# Main_MCU_Page_1.net
KiCad netlist of a schematic drawn in Altium Designer
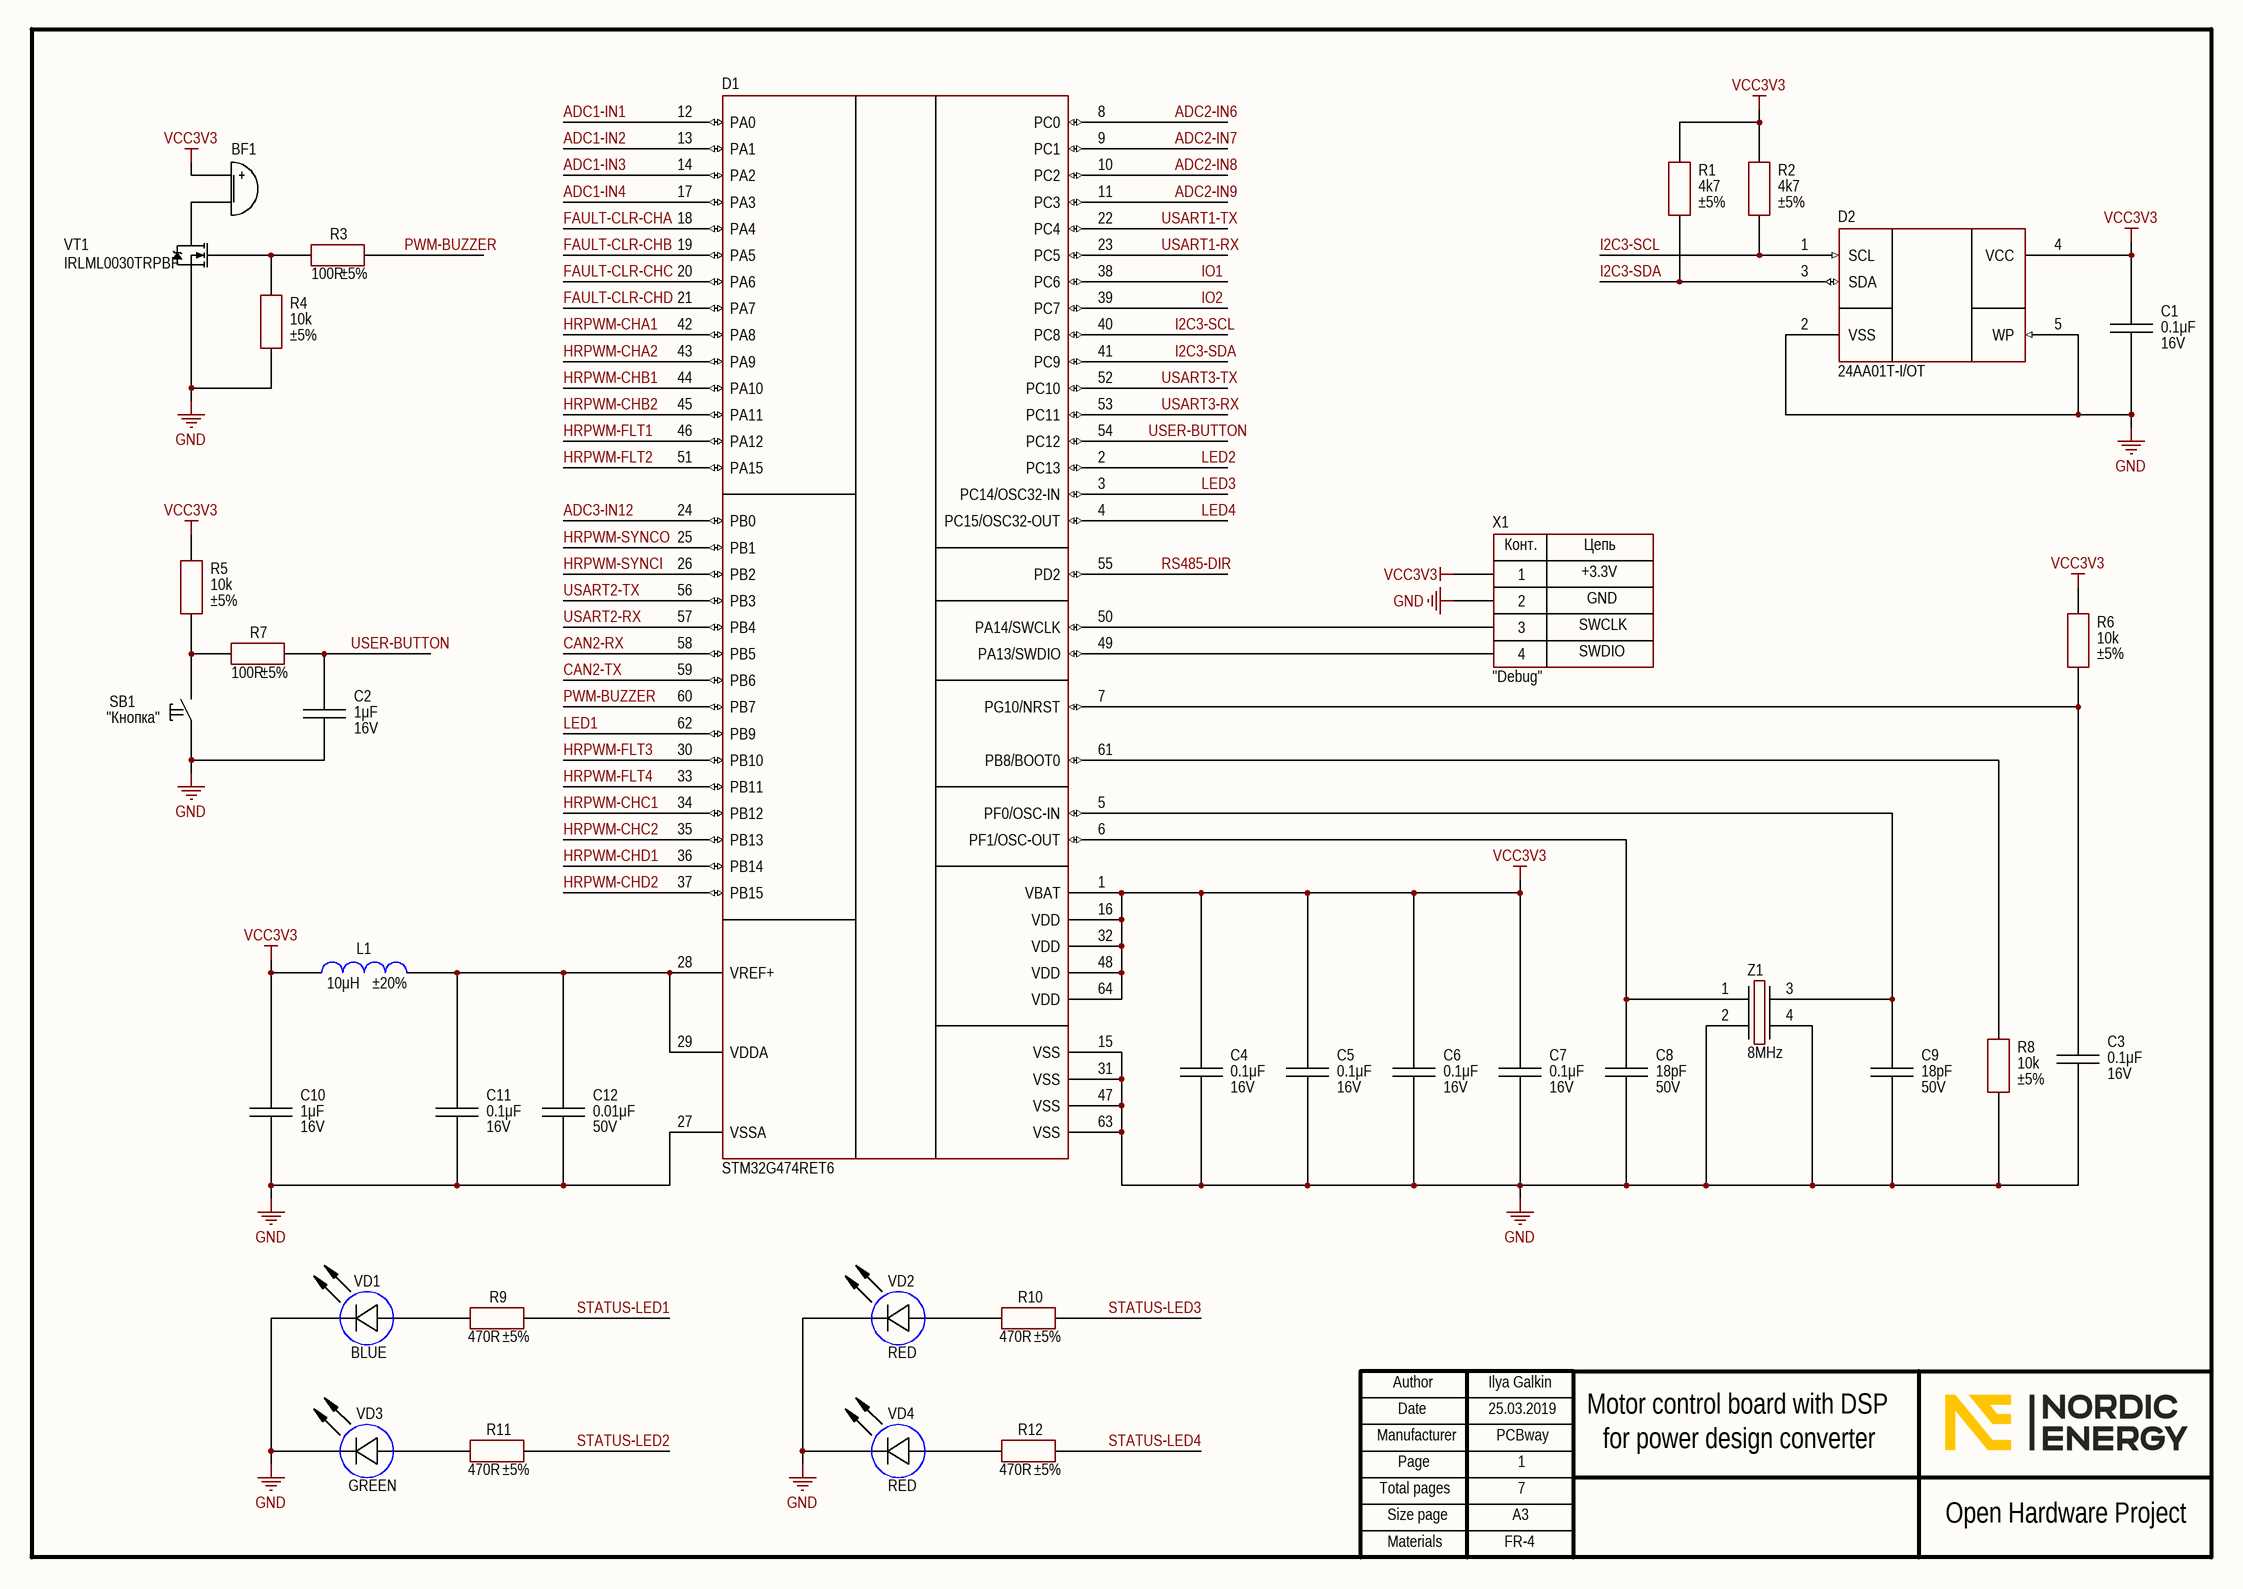
[diagram p0: Main MCU. Page 1.SchDoc]

(export (version "E")
  (design (tool "Eeschema 10.0.6"))
  (components
    (comp (ref "BF1")
      (value "~")
      (footprint "BUZ: AT-0927-TT-6-R")
      (fields
        (field (name "MANUFACTURER") "PUI Audio")
        (field (name "VALUEMANUFACTURERPARTNUMBER") "DIP switch, 2.73 kHz, 3VDC, 80mA, -20...+70°C")
        (field (name "PARTNUMBER") "AT-0927-TT-6-R")
      )
      (libsource (lib "Electromechanics") (part "Buzzer"))
    )
    (comp (ref "C1")
      (value "0.1μF")
      (footprint "CAP: 0805")
      (fields
        (field (name "MANUFACTURER") "Yageo")
        (field (name "PARTNUMBER") "CC0805KRX7R7BB104")
        (field (name "VALUEMANUFACTURERPARTNUMBER") "Ceramic capacitor, 0.1μF, X7R, ±10%, 16V, 0805, -55...+125°C")
        (field (name "VOLTAGE") "16V")
      )
      (libsource (lib "Capacitor") (part "Ceramic_0805"))
    )
    (comp (ref "C2")
      (value "1μF")
      (footprint "CAP: 0805")
      (fields
        (field (name "MANUFACTURER") "Yageo")
        (field (name "PARTNUMBER") "CC0805KKX7R7BB105")
        (field (name "VALUEMANUFACTURERPARTNUMBER") "Ceramic capacitor, 1μF, X7R, ±10%, 16V, 0805, -55...+125°C")
        (field (name "VOLTAGE") "16V")
      )
      (libsource (lib "Capacitor") (part "Ceramic_0805"))
    )
    (comp (ref "C3")
      (value "0.1μF")
      (footprint "CAP: 0805")
      (fields
        (field (name "MANUFACTURER") "Yageo")
        (field (name "PARTNUMBER") "CC0805KRX7R7BB104")
        (field (name "VALUEMANUFACTURERPARTNUMBER") "Ceramic capacitor, 0.1μF, X7R, ±10%, 16V, 0805, -55...+125°C")
        (field (name "VOLTAGE") "16V")
      )
      (libsource (lib "Capacitor") (part "Ceramic_0805"))
    )
    (comp (ref "C4")
      (value "0.1μF")
      (footprint "CAP: 0805")
      (fields
        (field (name "MANUFACTURER") "Yageo")
        (field (name "PARTNUMBER") "CC0805KRX7R7BB104")
        (field (name "VALUEMANUFACTURERPARTNUMBER") "Ceramic capacitor, 0.1μF, X7R, ±10%, 16V, 0805, -55...+125°C")
        (field (name "VOLTAGE") "16V")
      )
      (libsource (lib "Capacitor") (part "Ceramic_0805"))
    )
    (comp (ref "C5")
      (value "0.1μF")
      (footprint "CAP: 0805")
      (fields
        (field (name "MANUFACTURER") "Yageo")
        (field (name "PARTNUMBER") "CC0805KRX7R7BB104")
        (field (name "VALUEMANUFACTURERPARTNUMBER") "Ceramic capacitor, 0.1μF, X7R, ±10%, 16V, 0805, -55...+125°C")
        (field (name "VOLTAGE") "16V")
      )
      (libsource (lib "Capacitor") (part "Ceramic_0805"))
    )
    (comp (ref "C6")
      (value "0.1μF")
      (footprint "CAP: 0805")
      (fields
        (field (name "MANUFACTURER") "Yageo")
        (field (name "PARTNUMBER") "CC0805KRX7R7BB104")
        (field (name "VALUEMANUFACTURERPARTNUMBER") "Ceramic capacitor, 0.1μF, X7R, ±10%, 16V, 0805, -55...+125°C")
        (field (name "VOLTAGE") "16V")
      )
      (libsource (lib "Capacitor") (part "Ceramic_0805"))
    )
    (comp (ref "C7")
      (value "0.1μF")
      (footprint "CAP: 0805")
      (fields
        (field (name "MANUFACTURER") "Yageo")
        (field (name "PARTNUMBER") "CC0805KRX7R7BB104")
        (field (name "VALUEMANUFACTURERPARTNUMBER") "Ceramic capacitor, 0.1μF, X7R, ±10%, 16V, 0805, -55...+125°C")
        (field (name "VOLTAGE") "16V")
      )
      (libsource (lib "Capacitor") (part "Ceramic_0805"))
    )
    (comp (ref "C8")
      (value "18pF")
      (footprint "CAP: 0805")
      (fields
        (field (name "MANUFACTURER") "Yageo")
        (field (name "PARTNUMBER") "CC0805JRNPO9BN180")
        (field (name "VALUEMANUFACTURERPARTNUMBER") "Ceramic capacitor, 18pF, NPO, ±10%, 50V, 0805, -55...+125°C")
        (field (name "VOLTAGE") "50V")
      )
      (libsource (lib "Capacitor") (part "Ceramic_0805"))
    )
    (comp (ref "C9")
      (value "18pF")
      (footprint "CAP: 0805")
      (fields
        (field (name "MANUFACTURER") "Yageo")
        (field (name "PARTNUMBER") "CC0805JRNPO9BN180")
        (field (name "VALUEMANUFACTURERPARTNUMBER") "Ceramic capacitor, 18pF, NPO, ±10%, 50V, 0805, -55...+125°C")
        (field (name "VOLTAGE") "50V")
      )
      (libsource (lib "Capacitor") (part "Ceramic_0805"))
    )
    (comp (ref "C10")
      (value "1μF")
      (footprint "CAP: 0805")
      (fields
        (field (name "MANUFACTURER") "Yageo")
        (field (name "PARTNUMBER") "CC0805KKX7R7BB105")
        (field (name "VALUEMANUFACTURERPARTNUMBER") "Ceramic capacitor, 1μF, X7R, ±10%, 16V, 0805, -55...+125°C")
        (field (name "VOLTAGE") "16V")
      )
      (libsource (lib "Capacitor") (part "Ceramic_0805"))
    )
    (comp (ref "C11")
      (value "0.1μF")
      (footprint "CAP: 0805")
      (fields
        (field (name "MANUFACTURER") "Yageo")
        (field (name "PARTNUMBER") "CC0805KRX7R7BB104")
        (field (name "VALUEMANUFACTURERPARTNUMBER") "Ceramic capacitor, 0.1μF, X7R, ±10%, 16V, 0805, -55...+125°C")
        (field (name "VOLTAGE") "16V")
      )
      (libsource (lib "Capacitor") (part "Ceramic_0805"))
    )
    (comp (ref "C12")
      (value "0.01μF")
      (footprint "CAP: 0805")
      (fields
        (field (name "MANUFACTURER") "Yageo")
        (field (name "PARTNUMBER") "CC0805KRX7R9BB103")
        (field (name "VALUEMANUFACTURERPARTNUMBER") "Ceramic capacitor, 0.01μF, X7R, ±10%, 50V, 0805, -55...+125°C")
        (field (name "VOLTAGE") "50V")
      )
      (libsource (lib "Capacitor") (part "Ceramic_0805"))
    )
    (comp (ref "D1")
      (value "~")
      (footprint "64-LQFP")
      (description "Cortex-M4")
      (fields
        (field (name "MANUFACTURER") "STMicroelectronics")
        (field (name "VALUEMANUFACTURERPARTNUMBER") "IC microcontroller, 32-Bit, Cortex-M4, 170MHz, 512KB, 128KB, 1.71...3.6V, -40...+85°C, 64-LQFP")
        (field (name "PARTNUMBER") "STM32G474RET6")
      )
      (libsource (lib "IC. MCU") (part "STM32G474RET6"))
    )
    (comp (ref "D2")
      (value "~")
      (footprint "SOT23-5")
      (description "EEPROM")
      (fields
        (field (name "MANUFACTURER") "Microchip Technology")
        (field (name "VALUEMANUFACTURERPARTNUMBER") "IC memory, EEPROM, 1KB (128x8), 400 kHz, I2C, 1.7...5.5V, -40...+85°C, SOT-23-5")
        (field (name "PARTNUMBER") "24AA01T-I/OT")
      )
      (libsource (lib "IC. Memory") (part "24AA01T"))
    )
    (comp (ref "L1")
      (value "10μH")
      (footprint "IND: 0805")
      (fields
        (field (name "MANUFACTURER") "Murata Electronics")
        (field (name "PARTNUMBER") "LQM21FN100M70L")
        (field (name "VALUEMANUFACTURERPARTNUMBER") "Fixed inductor, 10μH, ±20%, 0805, 100mA, -55...+125°C")
        (field (name "TOLERANCE") "±20%")
      )
      (libsource (lib "Inductor") (part "Inductor_0805"))
    )
    (comp (ref "R1")
      (value "4k7")
      (footprint "RES: 0805")
      (fields
        (field (name "MANUFACTURER") "Yageo")
        (field (name "PARTNUMBER") "RC0805JR-074K7L")
        (field (name "VALUEMANUFACTURERPARTNUMBER") "Resistor film, 4k7, ±5%, 0805, 0.125W, -55...+125°C")
        (field (name "TOLERANCE") "±5%")
      )
      (libsource (lib "Resistor") (part "Resistor_0805"))
    )
    (comp (ref "R2")
      (value "4k7")
      (footprint "RES: 0805")
      (fields
        (field (name "MANUFACTURER") "Yageo")
        (field (name "PARTNUMBER") "RC0805JR-074K7L")
        (field (name "VALUEMANUFACTURERPARTNUMBER") "Resistor film, 4k7, ±5%, 0805, 0.125W, -55...+125°C")
        (field (name "TOLERANCE") "±5%")
      )
      (libsource (lib "Resistor") (part "Resistor_0805"))
    )
    (comp (ref "R3")
      (value "100R")
      (footprint "RES: 0805")
      (fields
        (field (name "MANUFACTURER") "Yageo")
        (field (name "PARTNUMBER") "RC0805JR-07100RL")
        (field (name "VALUEMANUFACTURERPARTNUMBER") "Resistor film, 100R, ±5%, 0805, 0.125W, -55...+125°C")
        (field (name "TOLERANCE") "±5%")
      )
      (libsource (lib "") (part "Resistor_0805_1"))
    )
    (comp (ref "R4")
      (value "10k")
      (footprint "RES: 0805")
      (fields
        (field (name "MANUFACTURER") "Yageo")
        (field (name "PARTNUMBER") "RC0805JR-0710KL")
        (field (name "VALUEMANUFACTURERPARTNUMBER") "Resistor film, 10k, ±5%, 0805, 0.125W, -55...+125°C")
        (field (name "TOLERANCE") "±5%")
      )
      (libsource (lib "Resistor") (part "Resistor_0805"))
    )
    (comp (ref "R5")
      (value "10k")
      (footprint "RES: 0805")
      (fields
        (field (name "MANUFACTURER") "Yageo")
        (field (name "PARTNUMBER") "RC0805JR-0710KL")
        (field (name "VALUEMANUFACTURERPARTNUMBER") "Resistor film, 10k, ±5%, 0805, 0.125W, -55...+125°C")
        (field (name "TOLERANCE") "±5%")
      )
      (libsource (lib "Resistor") (part "Resistor_0805"))
    )
    (comp (ref "R6")
      (value "10k")
      (footprint "RES: 0805")
      (fields
        (field (name "MANUFACTURER") "Yageo")
        (field (name "PARTNUMBER") "RC0805JR-0710KL")
        (field (name "VALUEMANUFACTURERPARTNUMBER") "Resistor film, 10k, ±5%, 0805, 0.125W, -55...+125°C")
        (field (name "TOLERANCE") "±5%")
      )
      (libsource (lib "Resistor") (part "Resistor_0805"))
    )
    (comp (ref "R7")
      (value "100R")
      (footprint "RES: 0805")
      (fields
        (field (name "MANUFACTURER") "Yageo")
        (field (name "PARTNUMBER") "RC0805JR-07100RL")
        (field (name "VALUEMANUFACTURERPARTNUMBER") "Resistor film, 100R, ±5%, 0805, 0.125W, -55...+125°C")
        (field (name "TOLERANCE") "±5%")
      )
      (libsource (lib "") (part "Resistor_0805_1"))
    )
    (comp (ref "R8")
      (value "10k")
      (footprint "RES: 0805")
      (fields
        (field (name "MANUFACTURER") "Yageo")
        (field (name "PARTNUMBER") "RC0805JR-0710KL")
        (field (name "VALUEMANUFACTURERPARTNUMBER") "Resistor film, 10k, ±5%, 0805, 0.125W, -55...+125°C")
        (field (name "TOLERANCE") "±5%")
      )
      (libsource (lib "Resistor") (part "Resistor_0805"))
    )
    (comp (ref "R9")
      (value "470R")
      (footprint "RES: 0805")
      (fields
        (field (name "MANUFACTURER") "Yageo")
        (field (name "PARTNUMBER") "RC0805JR-07470RL")
        (field (name "VALUEMANUFACTURERPARTNUMBER") "Resistor film, 470R, ±5%, 0805, 0.125W, -55...+125°C")
        (field (name "TOLERANCE") "±5%")
      )
      (libsource (lib "") (part "Resistor_0805_1"))
    )
    (comp (ref "R10")
      (value "470R")
      (footprint "RES: 0805")
      (fields
        (field (name "MANUFACTURER") "Yageo")
        (field (name "PARTNUMBER") "RC0805JR-07470RL")
        (field (name "VALUEMANUFACTURERPARTNUMBER") "Resistor film, 470R, ±5%, 0805, 0.125W, -55...+125°C")
        (field (name "TOLERANCE") "±5%")
      )
      (libsource (lib "") (part "Resistor_0805_1"))
    )
    (comp (ref "R11")
      (value "470R")
      (footprint "RES: 0805")
      (fields
        (field (name "MANUFACTURER") "Yageo")
        (field (name "PARTNUMBER") "RC0805JR-07470RL")
        (field (name "VALUEMANUFACTURERPARTNUMBER") "Resistor film, 470R, ±5%, 0805, 0.125W, -55...+125°C")
        (field (name "TOLERANCE") "±5%")
      )
      (libsource (lib "") (part "Resistor_0805_1"))
    )
    (comp (ref "R12")
      (value "470R")
      (footprint "RES: 0805")
      (fields
        (field (name "MANUFACTURER") "Yageo")
        (field (name "PARTNUMBER") "RC0805JR-07470RL")
        (field (name "VALUEMANUFACTURERPARTNUMBER") "Resistor film, 470R, ±5%, 0805, 0.125W, -55...+125°C")
        (field (name "TOLERANCE") "±5%")
      )
      (libsource (lib "") (part "Resistor_0805_1"))
    )
    (comp (ref "SB1")
      (value "~")
      (footprint "BUT: 6x6 SMD")
      (fields
        (field (name "MANUFACTURER") "TE Connectivity")
        (field (name "VALUEMANUFACTURERPARTNUMBER") "Tactile button, 6x6mm")
        (field (name "PARTNUMBER") "FSM2JSMAATR")
        (field (name "COMMENTTEXT") "\"Кнопка\"")
      )
      (libsource (lib "Electromechanics") (part "Button_tactile"))
    )
    (comp (ref "VD1")
      (value "~")
      (footprint "LED: 0805B")
      (fields
        (field (name "MANUFACTURER") "Wurth")
        (field (name "VALUEMANUFACTURERPARTNUMBER") "LED, 20mA, 3.2V, 0805, -55...+150°C")
        (field (name "PARTNUMBER") "150080BS75000")
        (field (name "COLOR") "BLUE")
      )
      (libsource (lib "Diode") (part "LED_single"))
    )
    (comp (ref "VD2")
      (value "~")
      (footprint "LED: 0805R")
      (fields
        (field (name "MANUFACTURER") "Wurth")
        (field (name "VALUEMANUFACTURERPARTNUMBER") "LED, 20mA, 2V, 0805, -55...+150°C")
        (field (name "PARTNUMBER") "150080RS75000")
        (field (name "COLOR") "RED")
      )
      (libsource (lib "Diode") (part "LED_single"))
    )
    (comp (ref "VD3")
      (value "~")
      (footprint "LED: 0603G")
      (fields
        (field (name "MANUFACTURER") "Wurth")
        (field (name "VALUEMANUFACTURERPARTNUMBER") "LED, 20mA, 2V, 0805, -55...+150°C")
        (field (name "PARTNUMBER") "150080VS75000")
        (field (name "COLOR") "GREEN")
      )
      (libsource (lib "Diode") (part "LED_single"))
    )
    (comp (ref "VD4")
      (value "~")
      (footprint "LED: 0805R")
      (fields
        (field (name "MANUFACTURER") "Wurth")
        (field (name "VALUEMANUFACTURERPARTNUMBER") "LED, 20mA, 2V, 0805, -55...+150°C")
        (field (name "PARTNUMBER") "150080RS75000")
        (field (name "COLOR") "RED")
      )
      (libsource (lib "Diode") (part "LED_single"))
    )
    (comp (ref "VT1")
      (value "~")
      (footprint "SOT23")
      (fields
        (field (name "MANUFACTURER") "Infineon Technologies")
        (field (name "VALUEMANUFACTURERPARTNUMBER") "MOSFET N-channel transistor, 30V, 5.3A, 2.6nC, 2.5W, 27mOhm, 382pF, SOT-23, -55...+150°C")
        (field (name "PARTNUMBER") "IRLML0030TRPBF")
      )
      (libsource (lib "Transistor") (part "MOSFET_N_132"))
    )
    (comp (ref "X1")
      (value "~")
      (footprint "CON: SM04B-GHS")
      (fields
        (field (name "MANUFACTURER") "JST")
        (field (name "VALUEMANUFACTURERPARTNUMBER") "Connector, 4pin, 1.25mm, 50VDC, 1A")
        (field (name "PARTNUMBER") "SM04B-GHS")
        (field (name "COMMENTTEXT") "\"Debug\"")
      )
      (libsource (lib "Connector") (part "Connector_SM04B"))
    )
    (comp (ref "Z1")
      (value "~")
      (footprint "OSC: 5032")
      (fields
        (field (name "MANUFACTURER") "Diodes Incorporated")
        (field (name "PARTNUMBER") "ABM3B-8.000MHZ-B2-T")
        (field (name "VALUEMANUFACTURERPARTNUMBER") "Crystal, 8MHz, 18pF, ±30ppm, case 5032, -20...+70°C")
        (field (name "FREQUENCY") "8MHz")
      )
      (libsource (lib "Oscilator") (part "Crystal_5032"))
    )
  )
  (nets
    (net (code "1") (name "/ADC1-IN1") (class "Default")
      (node (ref "D1") (pin "12") (pinfunction "PA0_12") (pintype "bidirectional"))
    )
    (net (code "2") (name "/ADC1-IN2") (class "Default")
      (node (ref "D1") (pin "13") (pinfunction "PA1_13") (pintype "bidirectional"))
    )
    (net (code "3") (name "/ADC1-IN3") (class "Default")
      (node (ref "D1") (pin "14") (pinfunction "PA2_14") (pintype "bidirectional"))
    )
    (net (code "4") (name "/ADC1-IN4") (class "Default")
      (node (ref "D1") (pin "17") (pinfunction "PA3_17") (pintype "bidirectional"))
    )
    (net (code "5") (name "/ADC2-IN6") (class "Default")
      (node (ref "D1") (pin "8") (pinfunction "PC0_8") (pintype "bidirectional"))
    )
    (net (code "6") (name "/ADC2-IN7") (class "Default")
      (node (ref "D1") (pin "9") (pinfunction "PC1_9") (pintype "bidirectional"))
    )
    (net (code "7") (name "/ADC2-IN8") (class "Default")
      (node (ref "D1") (pin "10") (pinfunction "PC2_10") (pintype "bidirectional"))
    )
    (net (code "8") (name "/ADC2-IN9") (class "Default")
      (node (ref "D1") (pin "11") (pinfunction "PC3_11") (pintype "bidirectional"))
    )
    (net (code "9") (name "/ADC3-IN12") (class "Default")
      (node (ref "D1") (pin "24") (pinfunction "PB0_24") (pintype "bidirectional"))
    )
    (net (code "10") (name "/CAN2-RX") (class "Default")
      (node (ref "D1") (pin "58") (pinfunction "PB5_58") (pintype "bidirectional"))
    )
    (net (code "11") (name "/CAN2-TX") (class "Default")
      (node (ref "D1") (pin "59") (pinfunction "PB6_59") (pintype "bidirectional"))
    )
    (net (code "12") (name "/FAULT-CLR-CHA") (class "Default")
      (node (ref "D1") (pin "18") (pinfunction "PA4_18") (pintype "bidirectional"))
    )
    (net (code "13") (name "/FAULT-CLR-CHB") (class "Default")
      (node (ref "D1") (pin "19") (pinfunction "PA5_19") (pintype "bidirectional"))
    )
    (net (code "14") (name "/FAULT-CLR-CHC") (class "Default")
      (node (ref "D1") (pin "20") (pinfunction "PA6_20") (pintype "bidirectional"))
    )
    (net (code "15") (name "/FAULT-CLR-CHD") (class "Default")
      (node (ref "D1") (pin "21") (pinfunction "PA7_21") (pintype "bidirectional"))
    )
    (net (code "16") (name "/HRPWM-CHA1") (class "Default")
      (node (ref "D1") (pin "42") (pinfunction "PA8_42") (pintype "bidirectional"))
    )
    (net (code "17") (name "/HRPWM-CHA2") (class "Default")
      (node (ref "D1") (pin "43") (pinfunction "PA9_43") (pintype "bidirectional"))
    )
    (net (code "18") (name "/HRPWM-CHB1") (class "Default")
      (node (ref "D1") (pin "44") (pinfunction "PA10_44") (pintype "bidirectional"))
    )
    (net (code "19") (name "/HRPWM-CHB2") (class "Default")
      (node (ref "D1") (pin "45") (pinfunction "PA11_45") (pintype "bidirectional"))
    )
    (net (code "20") (name "/HRPWM-CHC1") (class "Default")
      (node (ref "D1") (pin "34") (pinfunction "PB12_34") (pintype "bidirectional"))
    )
    (net (code "21") (name "/HRPWM-CHC2") (class "Default")
      (node (ref "D1") (pin "35") (pinfunction "PB13_35") (pintype "bidirectional"))
    )
    (net (code "22") (name "/HRPWM-CHD1") (class "Default")
      (node (ref "D1") (pin "36") (pinfunction "PB14_36") (pintype "bidirectional"))
    )
    (net (code "23") (name "/HRPWM-CHD2") (class "Default")
      (node (ref "D1") (pin "37") (pinfunction "PB15_37") (pintype "bidirectional"))
    )
    (net (code "24") (name "/HRPWM-FLT1") (class "Default")
      (node (ref "D1") (pin "46") (pinfunction "PA12_46") (pintype "bidirectional"))
    )
    (net (code "25") (name "/HRPWM-FLT2") (class "Default")
      (node (ref "D1") (pin "51") (pinfunction "PA15_51") (pintype "bidirectional"))
    )
    (net (code "26") (name "/HRPWM-FLT3") (class "Default")
      (node (ref "D1") (pin "30") (pinfunction "PB10_30") (pintype "bidirectional"))
    )
    (net (code "27") (name "/HRPWM-FLT4") (class "Default")
      (node (ref "D1") (pin "33") (pinfunction "PB11_33") (pintype "bidirectional"))
    )
    (net (code "28") (name "/HRPWM-SYNCI") (class "Default")
      (node (ref "D1") (pin "26") (pinfunction "PB2_26") (pintype "bidirectional"))
    )
    (net (code "29") (name "/HRPWM-SYNCO") (class "Default")
      (node (ref "D1") (pin "25") (pinfunction "PB1_25") (pintype "bidirectional"))
    )
    (net (code "30") (name "/I2C3-SCL") (class "Default")
      (node (ref "D1") (pin "40") (pinfunction "PC8_40") (pintype "bidirectional"))
      (node (ref "D2") (pin "1") (pinfunction "SCL_1") (pintype "input"))
      (node (ref "R2") (pin "2") (pinfunction "2_2") (pintype "passive"))
    )
    (net (code "31") (name "/I2C3-SDA") (class "Default")
      (node (ref "D1") (pin "41") (pinfunction "PC9_41") (pintype "bidirectional"))
      (node (ref "D2") (pin "3") (pinfunction "SDA_3") (pintype "bidirectional"))
      (node (ref "R1") (pin "2") (pinfunction "2_2") (pintype "passive"))
    )
    (net (code "32") (name "/IO1") (class "Default")
      (node (ref "D1") (pin "38") (pinfunction "PC6_38") (pintype "bidirectional"))
    )
    (net (code "33") (name "/IO2") (class "Default")
      (node (ref "D1") (pin "39") (pinfunction "PC7_39") (pintype "bidirectional"))
    )
    (net (code "34") (name "/LED1") (class "Default")
      (node (ref "D1") (pin "62") (pinfunction "PB9_62") (pintype "bidirectional"))
    )
    (net (code "35") (name "/LED2") (class "Default")
      (node (ref "D1") (pin "2") (pinfunction "PC13_2") (pintype "bidirectional"))
    )
    (net (code "36") (name "/LED3") (class "Default")
      (node (ref "D1") (pin "3") (pinfunction "PC14/OSC32-IN_3") (pintype "bidirectional"))
    )
    (net (code "37") (name "/LED4") (class "Default")
      (node (ref "D1") (pin "4") (pinfunction "PC15/OSC32-OUT_4") (pintype "bidirectional"))
    )
    (net (code "38") (name "/PWM-BUZZER") (class "Default")
      (node (ref "D1") (pin "60") (pinfunction "PB7_60") (pintype "bidirectional"))
      (node (ref "R3") (pin "2") (pinfunction "2_2") (pintype "passive"))
    )
    (net (code "39") (name "/RS485-DIR") (class "Default")
      (node (ref "D1") (pin "55") (pinfunction "PD2_55") (pintype "bidirectional"))
    )
    (net (code "40") (name "/STATUS-LED1") (class "Default")
      (node (ref "R9") (pin "2") (pinfunction "2_2") (pintype "passive"))
    )
    (net (code "41") (name "/STATUS-LED2") (class "Default")
      (node (ref "R11") (pin "2") (pinfunction "2_2") (pintype "passive"))
    )
    (net (code "42") (name "/STATUS-LED3") (class "Default")
      (node (ref "R10") (pin "2") (pinfunction "2_2") (pintype "passive"))
    )
    (net (code "43") (name "/STATUS-LED4") (class "Default")
      (node (ref "R12") (pin "2") (pinfunction "2_2") (pintype "passive"))
    )
    (net (code "44") (name "/USART1-RX") (class "Default")
      (node (ref "D1") (pin "23") (pinfunction "PC5_23") (pintype "bidirectional"))
    )
    (net (code "45") (name "/USART1-TX") (class "Default")
      (node (ref "D1") (pin "22") (pinfunction "PC4_22") (pintype "bidirectional"))
    )
    (net (code "46") (name "/USART2-RX") (class "Default")
      (node (ref "D1") (pin "57") (pinfunction "PB4_57") (pintype "bidirectional"))
    )
    (net (code "47") (name "/USART2-TX") (class "Default")
      (node (ref "D1") (pin "56") (pinfunction "PB3_56") (pintype "bidirectional"))
    )
    (net (code "48") (name "/USART3-RX") (class "Default")
      (node (ref "D1") (pin "53") (pinfunction "PC11_53") (pintype "bidirectional"))
    )
    (net (code "49") (name "/USART3-TX") (class "Default")
      (node (ref "D1") (pin "52") (pinfunction "PC10_52") (pintype "bidirectional"))
    )
    (net (code "50") (name "/USER-BUTTON") (class "Default")
      (node (ref "C2") (pin "2") (pinfunction "2_2") (pintype "power_in"))
      (node (ref "D1") (pin "54") (pinfunction "PC12_54") (pintype "bidirectional"))
      (node (ref "R7") (pin "2") (pinfunction "2_2") (pintype "passive"))
    )
    (net (code "51") (name "GND") (class "Default")
      (node (ref "C1") (pin "1") (pinfunction "1_1") (pintype "power_in"))
      (node (ref "C10") (pin "1") (pinfunction "1_1") (pintype "power_in"))
      (node (ref "C11") (pin "1") (pinfunction "1_1") (pintype "power_in"))
      (node (ref "C12") (pin "1") (pinfunction "1_1") (pintype "power_in"))
      (node (ref "C2") (pin "1") (pinfunction "1_1") (pintype "power_in"))
      (node (ref "C3") (pin "1") (pinfunction "1_1") (pintype "power_in"))
      (node (ref "C4") (pin "1") (pinfunction "1_1") (pintype "power_in"))
      (node (ref "C5") (pin "1") (pinfunction "1_1") (pintype "power_in"))
      (node (ref "C6") (pin "1") (pinfunction "1_1") (pintype "power_in"))
      (node (ref "C7") (pin "1") (pinfunction "1_1") (pintype "power_in"))
      (node (ref "C8") (pin "1") (pinfunction "1_1") (pintype "power_in"))
      (node (ref "C9") (pin "1") (pinfunction "1_1") (pintype "power_in"))
      (node (ref "D1") (pin "15") (pinfunction "VSS_15") (pintype "passive"))
      (node (ref "D1") (pin "27") (pinfunction "VSSA_27") (pintype "passive"))
      (node (ref "D1") (pin "31") (pinfunction "VSS_31") (pintype "passive"))
      (node (ref "D1") (pin "47") (pinfunction "VSS_47") (pintype "passive"))
      (node (ref "D1") (pin "63") (pinfunction "VSS_63") (pintype "passive"))
      (node (ref "D2") (pin "2") (pinfunction "VSS_2") (pintype "power_in"))
      (node (ref "D2") (pin "5") (pinfunction "WP_5") (pintype "input"))
      (node (ref "R4") (pin "2") (pinfunction "2_2") (pintype "passive"))
      (node (ref "R8") (pin "2") (pinfunction "2_2") (pintype "passive"))
      (node (ref "SB1") (pin "1") (pinfunction "1_1") (pintype "passive"))
      (node (ref "VD1") (pin "2") (pinfunction "C_2") (pintype "passive"))
      (node (ref "VD2") (pin "2") (pinfunction "C_2") (pintype "passive"))
      (node (ref "VD3") (pin "2") (pinfunction "C_2") (pintype "passive"))
      (node (ref "VD4") (pin "2") (pinfunction "C_2") (pintype "passive"))
      (node (ref "VT1") (pin "2") (pinfunction "S_2") (pintype "passive"))
      (node (ref "X1") (pin "2") (pinfunction "2_2") (pintype "passive"))
      (node (ref "Z1") (pin "2") (pinfunction "2_2") (pintype "passive"))
      (node (ref "Z1") (pin "4") (pinfunction "4_4") (pintype "passive"))
    )
    (net (code "52") (name "Net-(BF1--)") (class "Default")
      (node (ref "BF1") (pin "2") (pinfunction "-_2") (pintype "passive"))
      (node (ref "VT1") (pin "3") (pinfunction "D_3") (pintype "passive"))
    )
    (net (code "53") (name "Net-(D1-PA13{slash}SWDIO)") (class "Default")
      (node (ref "D1") (pin "49") (pinfunction "PA13/SWDIO_49") (pintype "bidirectional"))
      (node (ref "X1") (pin "4") (pinfunction "4_4") (pintype "power_in"))
    )
    (net (code "54") (name "Net-(D1-PA14{slash}SWCLK)") (class "Default")
      (node (ref "D1") (pin "50") (pinfunction "PA14/SWCLK_50") (pintype "bidirectional"))
      (node (ref "X1") (pin "3") (pinfunction "3_3") (pintype "power_in"))
    )
    (net (code "55") (name "Net-(D1-PB8{slash}BOOT0)") (class "Default")
      (node (ref "D1") (pin "61") (pinfunction "PB8/BOOT0_61") (pintype "bidirectional"))
      (node (ref "R8") (pin "1") (pinfunction "1_1") (pintype "passive"))
    )
    (net (code "56") (name "Net-(D1-PF0{slash}OSC-IN)") (class "Default")
      (node (ref "C9") (pin "2") (pinfunction "2_2") (pintype "power_in"))
      (node (ref "D1") (pin "5") (pinfunction "PF0/OSC-IN_5") (pintype "bidirectional"))
      (node (ref "Z1") (pin "3") (pinfunction "3_3") (pintype "passive"))
    )
    (net (code "57") (name "Net-(D1-PF1{slash}OSC-OUT)") (class "Default")
      (node (ref "C8") (pin "2") (pinfunction "2_2") (pintype "power_in"))
      (node (ref "D1") (pin "6") (pinfunction "PF1/OSC-OUT_6") (pintype "bidirectional"))
      (node (ref "Z1") (pin "1") (pinfunction "1_1") (pintype "passive"))
    )
    (net (code "58") (name "Net-(D1-PG10{slash}NRST)") (class "Default")
      (node (ref "C3") (pin "2") (pinfunction "2_2") (pintype "power_in"))
      (node (ref "D1") (pin "7") (pinfunction "PG10/NRST_7") (pintype "bidirectional"))
      (node (ref "R6") (pin "2") (pinfunction "2_2") (pintype "passive"))
    )
    (net (code "59") (name "Net-(D1-VDDA)") (class "Default")
      (node (ref "C11") (pin "2") (pinfunction "2_2") (pintype "power_in"))
      (node (ref "C12") (pin "2") (pinfunction "2_2") (pintype "power_in"))
      (node (ref "D1") (pin "28") (pinfunction "VREF+_28") (pintype "passive"))
      (node (ref "D1") (pin "29") (pinfunction "VDDA_29") (pintype "passive"))
      (node (ref "L1") (pin "1") (pinfunction "1_1") (pintype "passive"))
    )
    (net (code "60") (name "Net-(R5-Pad2)") (class "Default")
      (node (ref "R5") (pin "2") (pinfunction "2_2") (pintype "passive"))
      (node (ref "R7") (pin "1") (pinfunction "1_1") (pintype "passive"))
      (node (ref "SB1") (pin "2") (pinfunction "2_2") (pintype "passive"))
    )
    (net (code "61") (name "Net-(VD1-A)") (class "Default")
      (node (ref "R9") (pin "1") (pinfunction "1_1") (pintype "passive"))
      (node (ref "VD1") (pin "1") (pinfunction "A_1") (pintype "passive"))
    )
    (net (code "62") (name "Net-(VD2-A)") (class "Default")
      (node (ref "R10") (pin "1") (pinfunction "1_1") (pintype "passive"))
      (node (ref "VD2") (pin "1") (pinfunction "A_1") (pintype "passive"))
    )
    (net (code "63") (name "Net-(VD3-A)") (class "Default")
      (node (ref "R11") (pin "1") (pinfunction "1_1") (pintype "passive"))
      (node (ref "VD3") (pin "1") (pinfunction "A_1") (pintype "passive"))
    )
    (net (code "64") (name "Net-(VD4-A)") (class "Default")
      (node (ref "R12") (pin "1") (pinfunction "1_1") (pintype "passive"))
      (node (ref "VD4") (pin "1") (pinfunction "A_1") (pintype "passive"))
    )
    (net (code "65") (name "Net-(VT1-G)") (class "Default")
      (node (ref "R3") (pin "1") (pinfunction "1_1") (pintype "passive"))
      (node (ref "R4") (pin "1") (pinfunction "1_1") (pintype "passive"))
      (node (ref "VT1") (pin "1") (pinfunction "G_1") (pintype "passive"))
    )
    (net (code "66") (name "VCC3V3") (class "Default")
      (node (ref "BF1") (pin "1") (pinfunction "+_1") (pintype "passive"))
      (node (ref "C1") (pin "2") (pinfunction "2_2") (pintype "power_in"))
      (node (ref "C10") (pin "2") (pinfunction "2_2") (pintype "power_in"))
      (node (ref "C4") (pin "2") (pinfunction "2_2") (pintype "power_in"))
      (node (ref "C5") (pin "2") (pinfunction "2_2") (pintype "power_in"))
      (node (ref "C6") (pin "2") (pinfunction "2_2") (pintype "power_in"))
      (node (ref "C7") (pin "2") (pinfunction "2_2") (pintype "power_in"))
      (node (ref "D1") (pin "1") (pinfunction "VBAT_1") (pintype "passive"))
      (node (ref "D1") (pin "16") (pinfunction "VDD_16") (pintype "passive"))
      (node (ref "D1") (pin "32") (pinfunction "VDD_32") (pintype "passive"))
      (node (ref "D1") (pin "48") (pinfunction "VDD_48") (pintype "passive"))
      (node (ref "D1") (pin "64") (pinfunction "VDD_64") (pintype "passive"))
      (node (ref "D2") (pin "4") (pinfunction "VCC_4") (pintype "power_in"))
      (node (ref "L1") (pin "2") (pinfunction "2_2") (pintype "passive"))
      (node (ref "R1") (pin "1") (pinfunction "1_1") (pintype "passive"))
      (node (ref "R2") (pin "1") (pinfunction "1_1") (pintype "passive"))
      (node (ref "R5") (pin "1") (pinfunction "1_1") (pintype "passive"))
      (node (ref "R6") (pin "1") (pinfunction "1_1") (pintype "passive"))
      (node (ref "X1") (pin "1") (pinfunction "1_1") (pintype "passive"))
    )
  )
)
